# AD.net
KiCad netlist of a schematic drawn in Altium Designer
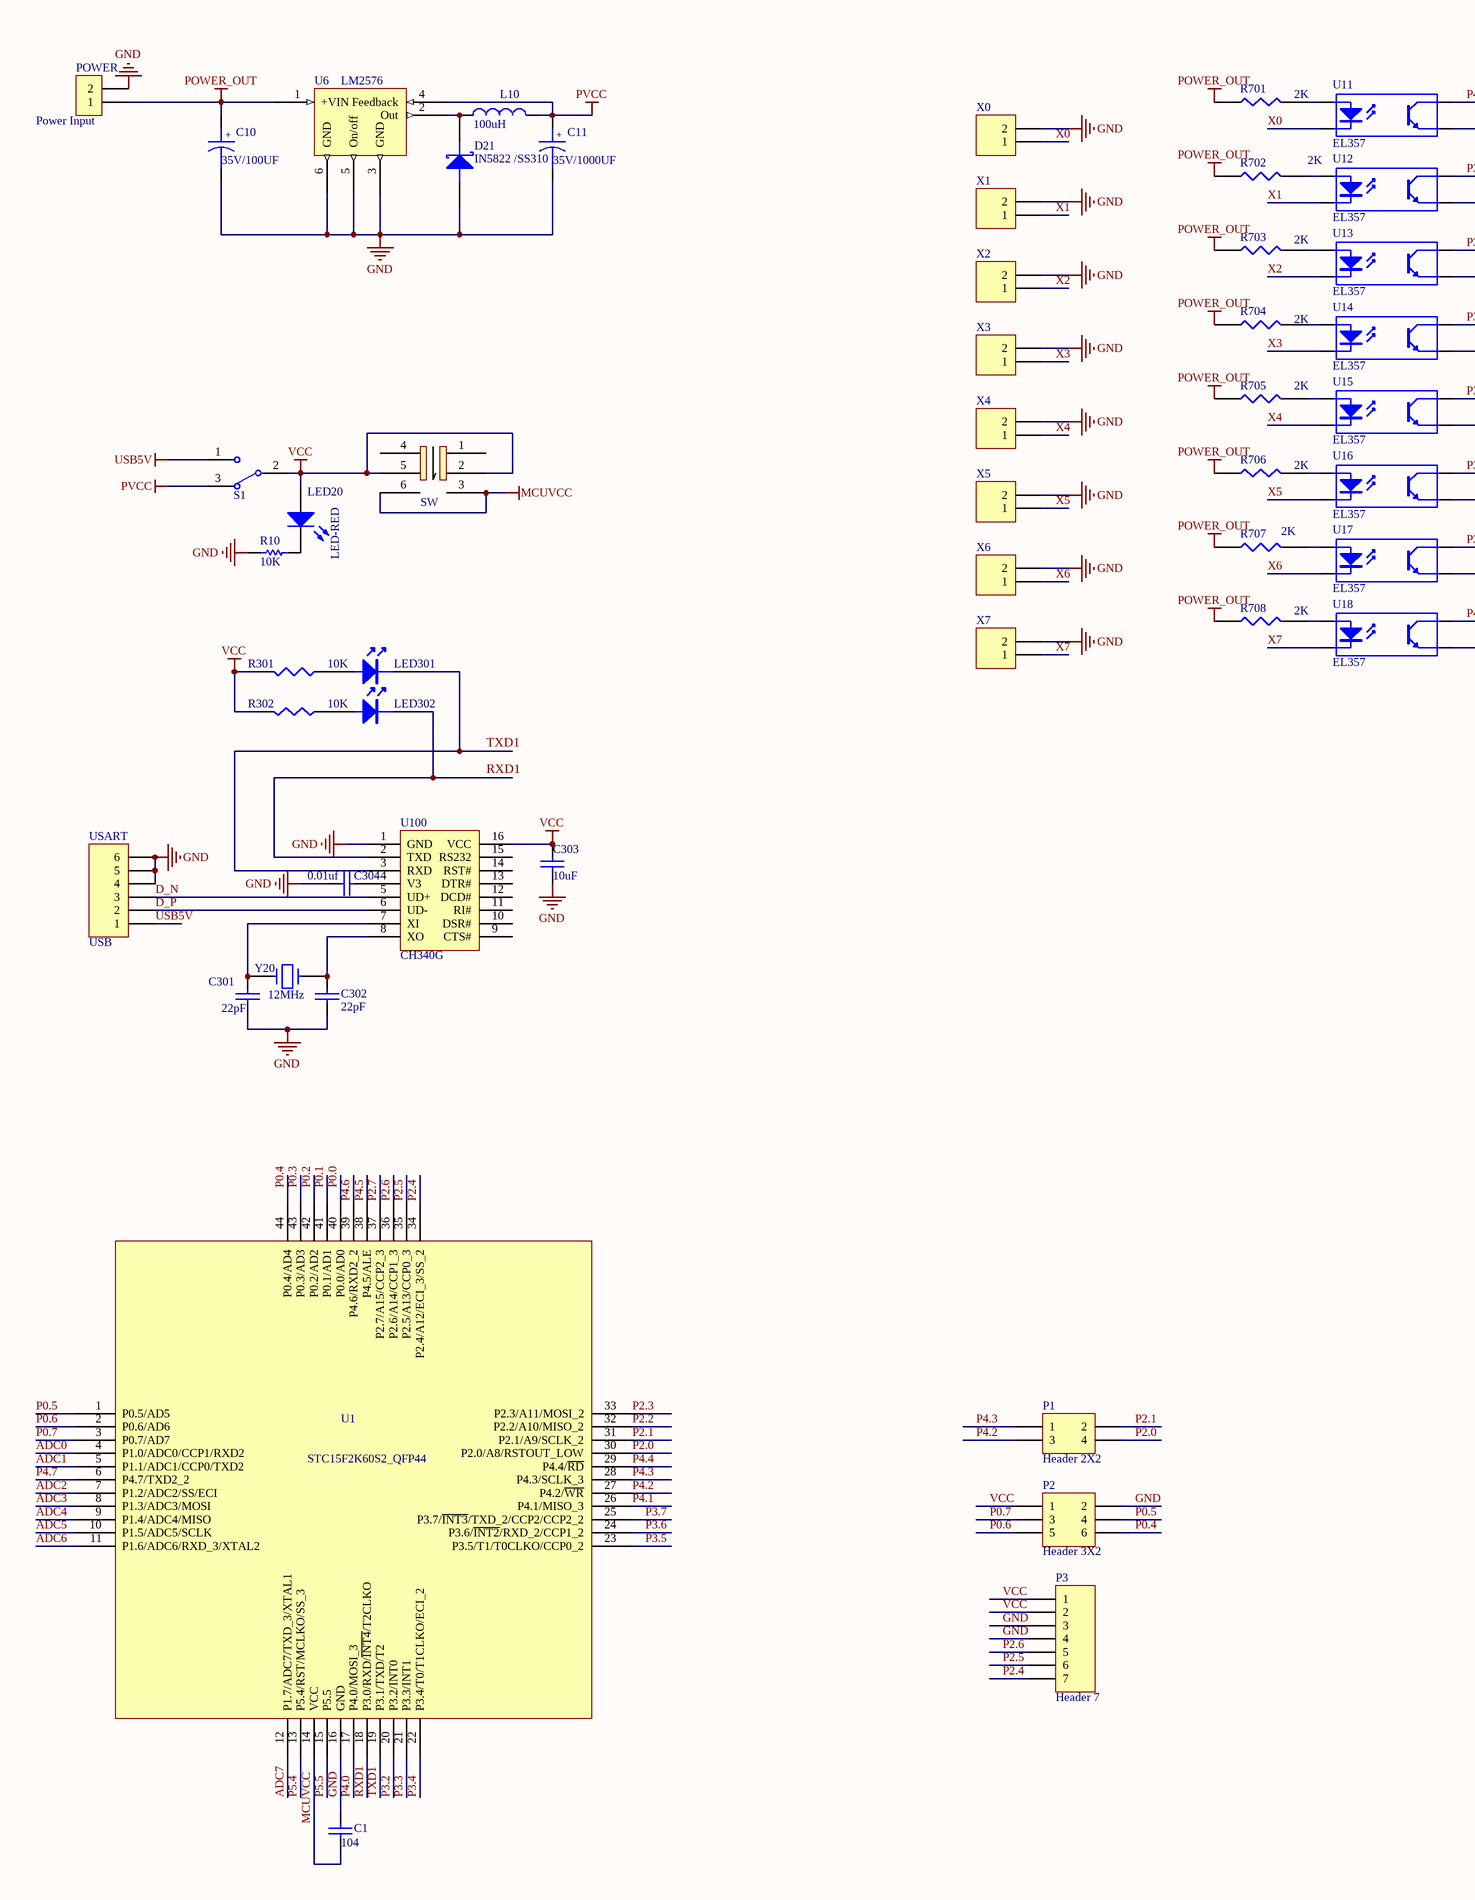
[diagram p0: AD.SchDoc, left]
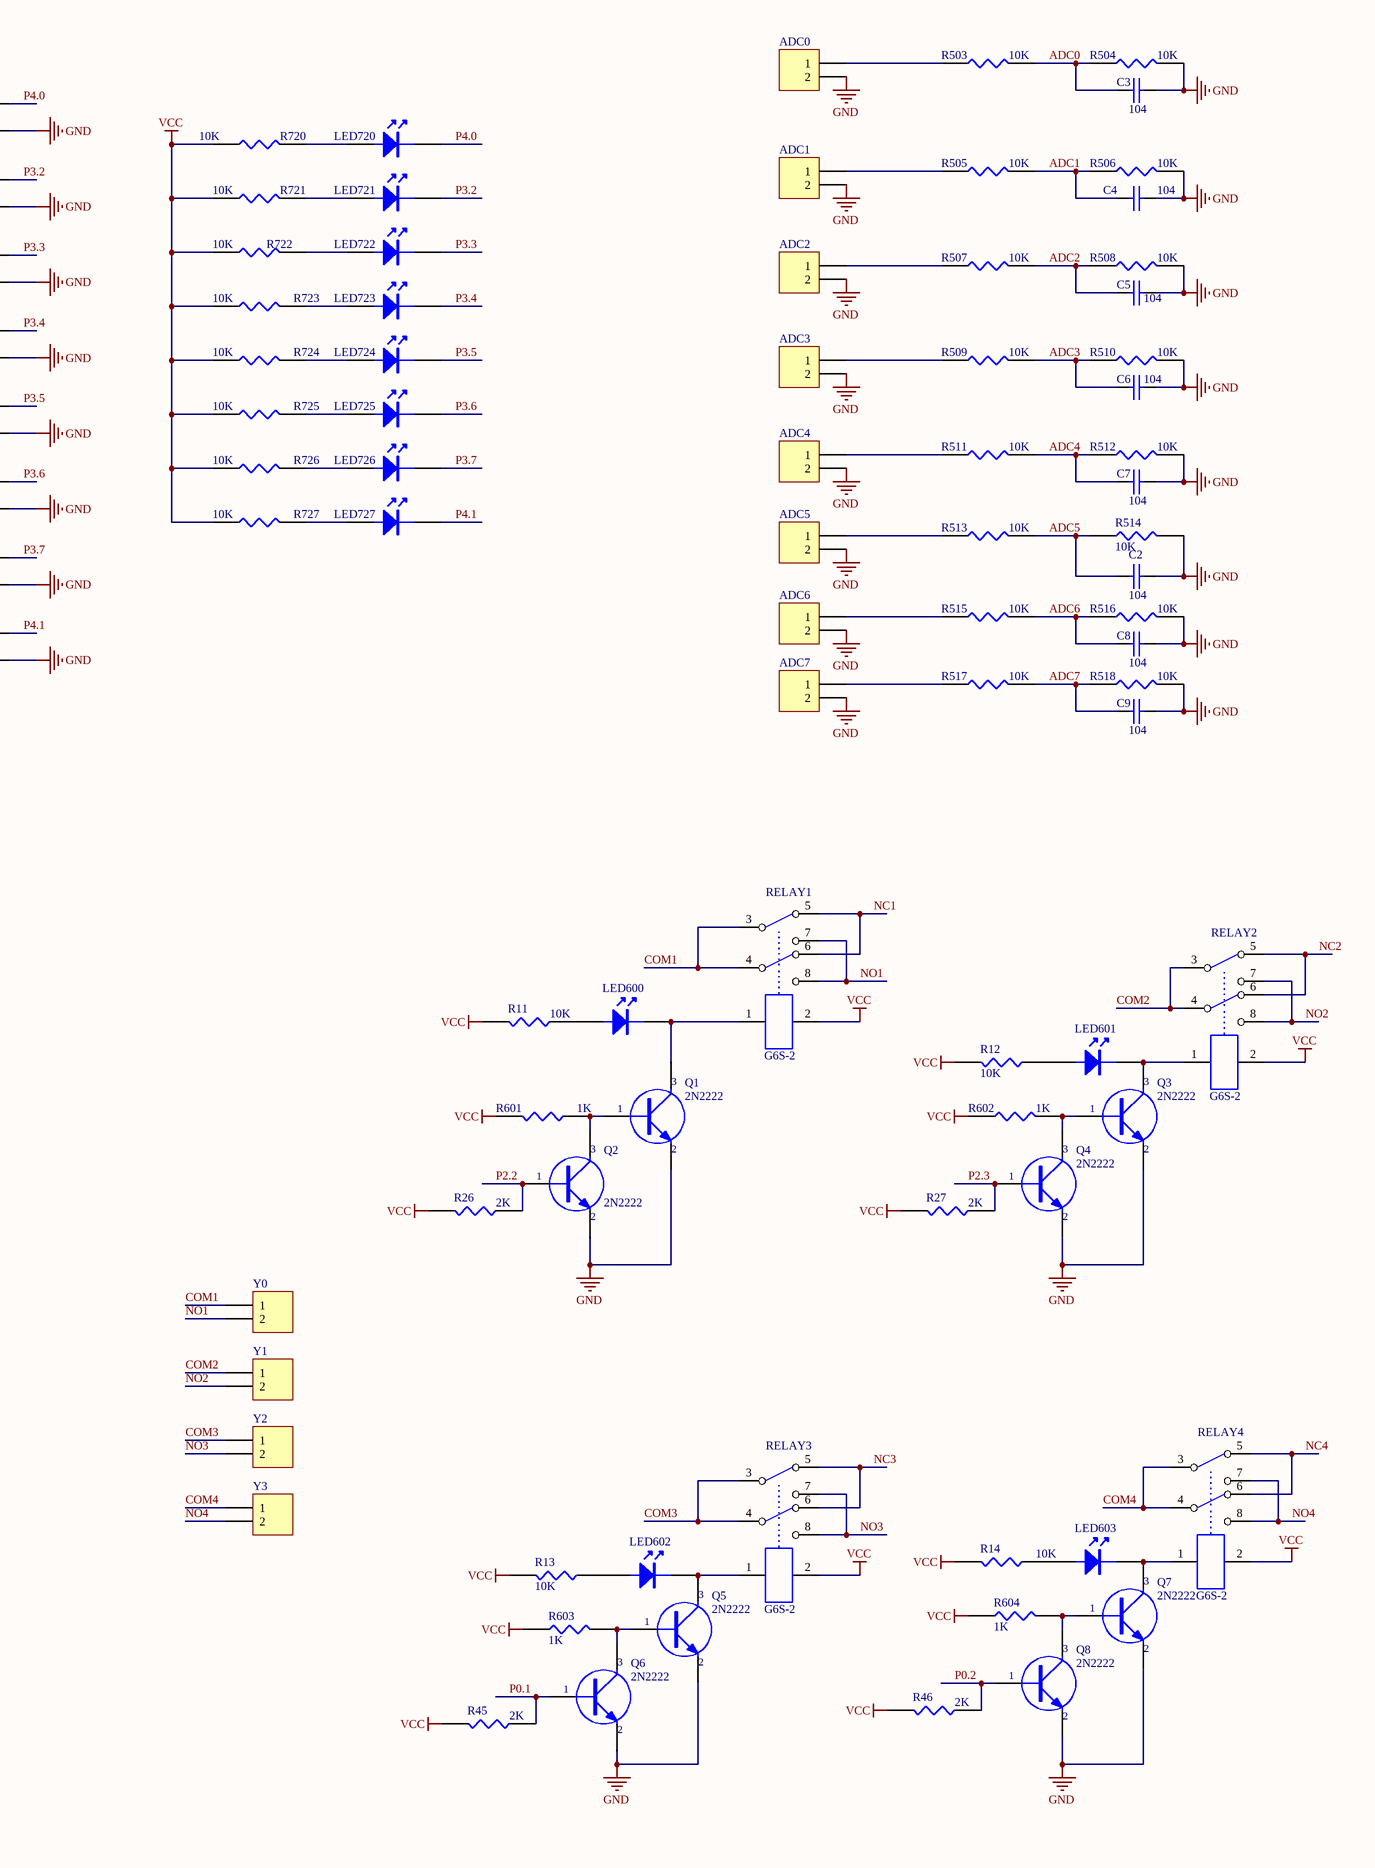
[diagram p1: AD.SchDoc, right]

(export (version "E")
  (design (tool "Eeschema 10.0.6"))
  (components
    (comp (ref "ADC0")
      (value "ADC")
      (footprint "CON2_1")
      (description "Header, 2-Pin")
      (fields (field (name "PUBLISHER") "Altium Limited"))
      (libsource (lib "") (part "Header 2_2"))
    )
    (comp (ref "ADC1")
      (value "ADC")
      (footprint "CON2_1")
      (description "Header, 2-Pin")
      (fields (field (name "PUBLISHER") "Altium Limited"))
      (libsource (lib "") (part "Header 2_2"))
    )
    (comp (ref "ADC2")
      (value "ADC")
      (footprint "CON2_1")
      (description "Header, 2-Pin")
      (fields (field (name "PUBLISHER") "Altium Limited"))
      (libsource (lib "") (part "Header 2_2"))
    )
    (comp (ref "ADC3")
      (value "ADC")
      (footprint "CON2_1")
      (description "Header, 2-Pin")
      (fields (field (name "PUBLISHER") "Altium Limited"))
      (libsource (lib "") (part "Header 2_2"))
    )
    (comp (ref "ADC4")
      (value "ADC")
      (footprint "CON2_1")
      (description "Header, 2-Pin")
      (fields (field (name "PUBLISHER") "Altium Limited"))
      (libsource (lib "") (part "Header 2_2"))
    )
    (comp (ref "ADC5")
      (value "ADC")
      (footprint "CON2_1")
      (description "Header, 2-Pin")
      (fields (field (name "PUBLISHER") "Altium Limited"))
      (libsource (lib "") (part "Header 2_2"))
    )
    (comp (ref "ADC6")
      (value "ADC")
      (footprint "CON2_1")
      (description "Header, 2-Pin")
      (fields (field (name "PUBLISHER") "Altium Limited"))
      (libsource (lib "") (part "Header 2_2"))
    )
    (comp (ref "ADC7")
      (value "ADC")
      (footprint "CON2_1")
      (description "Header, 2-Pin")
      (fields (field (name "PUBLISHER") "Altium Limited"))
      (libsource (lib "") (part "Header 2_2"))
    )
    (comp (ref "C1") (value "104") (footprint "R0805") (libsource (lib "brante_zhou") (part "CAP1")))
    (comp (ref "C2") (value "104") (footprint "R0805") (libsource (lib "brante_zhou") (part "CAP1")))
    (comp (ref "C3") (value "104") (footprint "R0805") (libsource (lib "brante_zhou") (part "CAP1")))
    (comp (ref "C4") (value "104") (footprint "R0805") (libsource (lib "brante_zhou") (part "CAP1")))
    (comp (ref "C5") (value "104") (footprint "R0805") (libsource (lib "brante_zhou") (part "CAP1")))
    (comp (ref "C6") (value "104") (footprint "R0805") (libsource (lib "brante_zhou") (part "CAP1")))
    (comp (ref "C7") (value "104") (footprint "R0805") (libsource (lib "brante_zhou") (part "CAP1")))
    (comp (ref "C8") (value "104") (footprint "R0805") (libsource (lib "brante_zhou") (part "CAP1")))
    (comp (ref "C9") (value "104") (footprint "R0805") (libsource (lib "brante_zhou") (part "CAP1")))
    (comp (ref "C10") (value "35V/100UF") (footprint "RB") (libsource (lib "My_Schlib") (part "CAP2")))
    (comp (ref "C11") (value "35V/1000UF") (footprint "L-DIP") (libsource (lib "My_Schlib") (part "CAP2")))
    (comp (ref "C301") (value "22pF") (footprint "C-0805") (libsource (lib "My_Schlib") (part "CAP1")))
    (comp (ref "C302") (value "22pF") (footprint "C-0805") (libsource (lib "My_Schlib") (part "CAP1")))
    (comp (ref "C303") (value "10uF") (footprint "R0805") (libsource (lib "My_Schlib") (part "CAP1")))
    (comp (ref "C304") (value "0.01uf") (footprint "C-0805") (libsource (lib "My_Schlib") (part "CAP1")))
    (comp (ref "D21")
      (value "IN5822 /SS310")
      (footprint "DO-214AC")
      (description "Schottky Diode")
      (libsource (lib "Miscellaneous Devices") (part "DIODE SCHOTTKY"))
    )
    (comp (ref "L10")
      (value "100uH")
      (footprint "L-DIP")
      (description "Inductor")
      (fields (field (name "PUBLISHER") "Altium Limited"))
      (libsource (lib "Miscellaneous Devices") (part "Inductor"))
    )
    (comp (ref "LED20")
      (value "LED-RED")
      (footprint "led-0805")
      (description "Typical INFRARED GaAs LED")
      (fields (field (name "PUBLISHER") "Altium Limited"))
      (libsource (lib "Miscellaneous Devices") (part "LED0"))
    )
    (comp (ref "LED301") (value "~") (footprint "LED-0805") (libsource (lib "*") (part "LED")))
    (comp (ref "LED302") (value "~") (footprint "LED-0805") (libsource (lib "*") (part "LED")))
    (comp (ref "LED600") (value "~") (footprint "LED-0805") (libsource (lib "brante_zhou") (part "LED")))
    (comp (ref "LED601") (value "~") (footprint "LED-0805") (libsource (lib "brante_zhou") (part "LED")))
    (comp (ref "LED602") (value "~") (footprint "LED-0805") (libsource (lib "brante_zhou") (part "LED")))
    (comp (ref "LED603") (value "~") (footprint "LED-0805") (libsource (lib "brante_zhou") (part "LED")))
    (comp (ref "LED720") (value "LED") (footprint "LED-0805") (libsource (lib "brante_zhou") (part "LED")))
    (comp (ref "LED721") (value "LED") (footprint "LED-0805") (libsource (lib "brante_zhou") (part "LED")))
    (comp (ref "LED722") (value "LED") (footprint "LED-0805") (libsource (lib "brante_zhou") (part "LED")))
    (comp (ref "LED723") (value "LED") (footprint "LED-0805") (libsource (lib "brante_zhou") (part "LED")))
    (comp (ref "LED724") (value "LED") (footprint "LED-0805") (libsource (lib "brante_zhou") (part "LED")))
    (comp (ref "LED725") (value "LED") (footprint "LED-0805") (libsource (lib "brante_zhou") (part "LED")))
    (comp (ref "LED726") (value "LED") (footprint "LED-0805") (libsource (lib "brante_zhou") (part "LED")))
    (comp (ref "LED727") (value "LED") (footprint "LED-0805") (libsource (lib "brante_zhou") (part "LED")))
    (comp (ref "P1")
      (value "Header 2X2")
      (footprint "HDR2X2")
      (description "Header, 2-Pin, Dual row")
      (fields (field (name "PUBLISHER") "Altium Limited"))
      (libsource (lib "Miscellaneous Connectors") (part "Header 2X2"))
    )
    (comp (ref "P2")
      (value "Header 3X2")
      (footprint "HDR2X3")
      (description "Header, 3-Pin, Dual row")
      (fields (field (name "PUBLISHER") "Altium Limited"))
      (libsource (lib "Miscellaneous Connectors") (part "Header 3X2"))
    )
    (comp (ref "P3")
      (value "Header 7")
      (footprint "HDR1X7")
      (description "Header, 7-Pin")
      (fields (field (name "PUBLISHER") "Altium Limited"))
      (libsource (lib "Miscellaneous Connectors") (part "Header 7"))
    )
    (comp (ref "POWER")
      (value "Power Input")
      (footprint "CON2_1")
      (libsource (lib "brante_zhou") (part "CON2"))
    )
    (comp (ref "Q1")
      (value "2N2222")
      (footprint "SOT23A")
      (description "NPN Transistor")
      (libsource (lib "My_Schlib") (part "NPN_S8050"))
    )
    (comp (ref "Q2")
      (value "2N2222")
      (footprint "SOT23A")
      (description "NPN Transistor")
      (libsource (lib "My_Schlib") (part "NPN_S8050"))
    )
    (comp (ref "Q3")
      (value "2N2222")
      (footprint "SOT23A")
      (description "NPN Transistor")
      (libsource (lib "My_Schlib") (part "NPN_S8050"))
    )
    (comp (ref "Q4")
      (value "2N2222")
      (footprint "SOT23A")
      (description "NPN Transistor")
      (libsource (lib "My_Schlib") (part "NPN_S8050"))
    )
    (comp (ref "Q5")
      (value "2N2222")
      (footprint "SOT23A")
      (description "NPN Transistor")
      (libsource (lib "My_Schlib") (part "NPN_S8050"))
    )
    (comp (ref "Q6")
      (value "2N2222")
      (footprint "SOT23A")
      (description "NPN Transistor")
      (libsource (lib "My_Schlib") (part "NPN_S8050"))
    )
    (comp (ref "Q7")
      (value "2N2222")
      (footprint "SOT23A")
      (description "NPN Transistor")
      (libsource (lib "My_Schlib") (part "NPN_S8050"))
    )
    (comp (ref "Q8")
      (value "2N2222")
      (footprint "SOT23A")
      (description "NPN Transistor")
      (libsource (lib "My_Schlib") (part "NPN_S8050"))
    )
    (comp (ref "R10")
      (value "10K")
      (footprint "R0805")
      (description "Semiconductor Resistor")
      (fields (field (name "PUBLISHER") "Altium Limited"))
      (libsource (lib "Miscellaneous Devices") (part "Res Semi"))
    )
    (comp (ref "R11") (value "10K") (footprint "R0805") (libsource (lib "brante_zhou") (part "RES")))
    (comp (ref "R12") (value "10K") (footprint "R0805") (libsource (lib "brante_zhou") (part "RES")))
    (comp (ref "R13") (value "10K") (footprint "R0805") (libsource (lib "brante_zhou") (part "RES")))
    (comp (ref "R14") (value "10K") (footprint "R0805") (libsource (lib "brante_zhou") (part "RES")))
    (comp (ref "R26") (value "2K") (footprint "R0805") (libsource (lib "brante_zhou") (part "RES")))
    (comp (ref "R27") (value "2K") (footprint "R0805") (libsource (lib "brante_zhou") (part "RES")))
    (comp (ref "R45") (value "2K") (footprint "R0805") (libsource (lib "brante_zhou") (part "RES")))
    (comp (ref "R46") (value "2K") (footprint "R0805") (libsource (lib "brante_zhou") (part "RES")))
    (comp (ref "R301")
      (value "10K")
      (footprint "R0805")
      (description "Resistor")
      (fields (field (name "PUBLISHER") "Altium Limited"))
      (libsource (lib "Miscellaneous Devices") (part "Res3"))
    )
    (comp (ref "R302")
      (value "10K")
      (footprint "R0805")
      (description "Resistor")
      (fields (field (name "PUBLISHER") "Altium Limited"))
      (libsource (lib "Miscellaneous Devices") (part "Res3"))
    )
    (comp (ref "R503") (value "10K") (footprint "R0805") (libsource (lib "brante_zhou") (part "RES")))
    (comp (ref "R504") (value "10K") (footprint "R0805") (libsource (lib "brante_zhou") (part "RES")))
    (comp (ref "R505") (value "10K") (footprint "R0805") (libsource (lib "brante_zhou") (part "RES")))
    (comp (ref "R506") (value "10K") (footprint "R0805") (libsource (lib "brante_zhou") (part "RES")))
    (comp (ref "R507") (value "10K") (footprint "R0805") (libsource (lib "brante_zhou") (part "RES")))
    (comp (ref "R508") (value "10K") (footprint "R0805") (libsource (lib "brante_zhou") (part "RES")))
    (comp (ref "R509") (value "10K") (footprint "R0805") (libsource (lib "brante_zhou") (part "RES")))
    (comp (ref "R510") (value "10K") (footprint "R0805") (libsource (lib "brante_zhou") (part "RES")))
    (comp (ref "R511") (value "10K") (footprint "R0805") (libsource (lib "brante_zhou") (part "RES")))
    (comp (ref "R512") (value "10K") (footprint "R0805") (libsource (lib "brante_zhou") (part "RES")))
    (comp (ref "R513") (value "10K") (footprint "R0805") (libsource (lib "brante_zhou") (part "RES")))
    (comp (ref "R514") (value "10K") (footprint "R0805") (libsource (lib "brante_zhou") (part "RES")))
    (comp (ref "R515") (value "10K") (footprint "R0805") (libsource (lib "brante_zhou") (part "RES")))
    (comp (ref "R516") (value "10K") (footprint "R0805") (libsource (lib "brante_zhou") (part "RES")))
    (comp (ref "R517") (value "10K") (footprint "R0805") (libsource (lib "brante_zhou") (part "RES")))
    (comp (ref "R518") (value "10K") (footprint "R0805") (libsource (lib "brante_zhou") (part "RES")))
    (comp (ref "R601") (value "1K") (footprint "R0805") (libsource (lib "brante_zhou") (part "RES")))
    (comp (ref "R602") (value "1K") (footprint "R0805") (libsource (lib "brante_zhou") (part "RES")))
    (comp (ref "R603") (value "1K") (footprint "R0805") (libsource (lib "brante_zhou") (part "RES")))
    (comp (ref "R604") (value "1K") (footprint "R0805") (libsource (lib "brante_zhou") (part "RES")))
    (comp (ref "R701") (value "2K") (footprint "R0805") (libsource (lib "brante_zhou") (part "RES")))
    (comp (ref "R702") (value "2K") (footprint "R0805") (libsource (lib "brante_zhou") (part "RES")))
    (comp (ref "R703") (value "2K") (footprint "R0805") (libsource (lib "brante_zhou") (part "RES")))
    (comp (ref "R704") (value "2K") (footprint "R0805") (libsource (lib "brante_zhou") (part "RES")))
    (comp (ref "R705") (value "2K") (footprint "R0805") (libsource (lib "brante_zhou") (part "RES")))
    (comp (ref "R706") (value "2K") (footprint "R0805") (libsource (lib "brante_zhou") (part "RES")))
    (comp (ref "R707") (value "2K") (footprint "R0805") (libsource (lib "brante_zhou") (part "RES")))
    (comp (ref "R708") (value "2K") (footprint "R0805") (libsource (lib "brante_zhou") (part "RES")))
    (comp (ref "R720") (value "10K") (footprint "R0805") (libsource (lib "brante_zhou") (part "RES")))
    (comp (ref "R721") (value "10K") (footprint "R0805") (libsource (lib "brante_zhou") (part "RES")))
    (comp (ref "R722") (value "10K") (footprint "R0805") (libsource (lib "brante_zhou") (part "RES")))
    (comp (ref "R723") (value "10K") (footprint "R0805") (libsource (lib "brante_zhou") (part "RES")))
    (comp (ref "R724") (value "10K") (footprint "R0805") (libsource (lib "brante_zhou") (part "RES")))
    (comp (ref "R725") (value "10K") (footprint "R0805") (libsource (lib "brante_zhou") (part "RES")))
    (comp (ref "R726") (value "10K") (footprint "R0805") (libsource (lib "brante_zhou") (part "RES")))
    (comp (ref "R727") (value "10K") (footprint "R0805") (libsource (lib "brante_zhou") (part "RES")))
    (comp (ref "RELAY1")
      (value "G6S-2")
      (footprint "G6S-2")
      (libsource (lib "My_Schlib") (part "RELAY-G6S-2"))
    )
    (comp (ref "RELAY2")
      (value "G6S-2")
      (footprint "G6S-2")
      (libsource (lib "My_Schlib") (part "RELAY-G6S-2"))
    )
    (comp (ref "RELAY3")
      (value "G6S-2")
      (footprint "G6S-2")
      (libsource (lib "My_Schlib") (part "RELAY-G6S-2"))
    )
    (comp (ref "RELAY4")
      (value "G6S-2")
      (footprint "G6S-2")
      (libsource (lib "My_Schlib") (part "RELAY-G6S-2"))
    )
    (comp (ref "S1")
      (value "SW-SPDT_2")
      (footprint "SW_1")
      (description "SPDT Subminiature Toggle Switch, Right Angle Mounting, Vertical Actuation")
      (fields (field (name "PUBLISHER") "Altium Limited"))
      (libsource (lib "My_Schlib") (part "SW-SPDT_2"))
    )
    (comp (ref "SW") (value "SW") (footprint "SW") (libsource (lib "RelayBoard") (part "SW")))
    (comp (ref "U1")
      (value "STC15F2K60S2_QFP44")
      (footprint "PQFP44")
      (libsource (lib "stcmcu_altium_lib") (part "STC15F2K60S2_QFP44"))
    )
    (comp (ref "U6") (value "LM2576") (footprint "LM2576") (libsource (lib "My_Schlib") (part "LM2576")))
    (comp (ref "U11")
      (value "EL357")
      (footprint "el357")
      (description "4-Pin Phototransistor Optocoupler")
      (fields (field (name "PUBLISHER") "Altium Limited"))
      (libsource (lib "My_Schlib") (part "Optoisolator"))
    )
    (comp (ref "U12")
      (value "EL357")
      (footprint "EL357")
      (description "4-Pin Phototransistor Optocoupler")
      (fields (field (name "PUBLISHER") "Altium Limited"))
      (libsource (lib "My_Schlib") (part "Optoisolator"))
    )
    (comp (ref "U13")
      (value "EL357")
      (footprint "EL357")
      (description "4-Pin Phototransistor Optocoupler")
      (fields (field (name "PUBLISHER") "Altium Limited"))
      (libsource (lib "My_Schlib") (part "Optoisolator"))
    )
    (comp (ref "U14")
      (value "EL357")
      (footprint "EL357")
      (description "4-Pin Phototransistor Optocoupler")
      (fields (field (name "PUBLISHER") "Altium Limited"))
      (libsource (lib "My_Schlib") (part "Optoisolator"))
    )
    (comp (ref "U15")
      (value "EL357")
      (footprint "EL357")
      (description "4-Pin Phototransistor Optocoupler")
      (fields (field (name "PUBLISHER") "Altium Limited"))
      (libsource (lib "My_Schlib") (part "Optoisolator"))
    )
    (comp (ref "U16")
      (value "EL357")
      (footprint "EL357")
      (description "4-Pin Phototransistor Optocoupler")
      (fields (field (name "PUBLISHER") "Altium Limited"))
      (libsource (lib "My_Schlib") (part "Optoisolator"))
    )
    (comp (ref "U17")
      (value "EL357")
      (footprint "EL357")
      (description "4-Pin Phototransistor Optocoupler")
      (fields (field (name "PUBLISHER") "Altium Limited"))
      (libsource (lib "My_Schlib") (part "Optoisolator"))
    )
    (comp (ref "U18")
      (value "EL357")
      (footprint "EL357")
      (description "4-Pin Phototransistor Optocoupler")
      (fields (field (name "PUBLISHER") "Altium Limited"))
      (libsource (lib "My_Schlib") (part "Optoisolator"))
    )
    (comp (ref "U100") (value "CH340G") (footprint "CH340G") (libsource (lib "My_Schlib") (part "CH340G")))
    (comp (ref "USART")
      (value "USB")
      (footprint "USB2.0_A")
      (description "Header, 6-Pin")
      (fields (field (name "PUBLISHER") "Altium Limited"))
      (libsource (lib "Miscellaneous Connectors") (part "Header 6"))
    )
    (comp (ref "X0")
      (value "XH2.54")
      (footprint "con2_1")
      (description "Header, 2-Pin")
      (fields (field (name "PUBLISHER") "Altium Limited"))
      (libsource (lib "") (part "Header 2_1"))
    )
    (comp (ref "X1")
      (value "XH2.54")
      (footprint "con2_1")
      (description "Header, 2-Pin")
      (fields (field (name "PUBLISHER") "Altium Limited"))
      (libsource (lib "") (part "Header 2_1"))
    )
    (comp (ref "X2")
      (value "XH2.54")
      (footprint "con2_1")
      (description "Header, 2-Pin")
      (fields (field (name "PUBLISHER") "Altium Limited"))
      (libsource (lib "") (part "Header 2_1"))
    )
    (comp (ref "X3")
      (value "XH2.54")
      (footprint "con2_1")
      (description "Header, 2-Pin")
      (fields (field (name "PUBLISHER") "Altium Limited"))
      (libsource (lib "") (part "Header 2_1"))
    )
    (comp (ref "X4")
      (value "XH2.54")
      (footprint "con2_1")
      (description "Header, 2-Pin")
      (fields (field (name "PUBLISHER") "Altium Limited"))
      (libsource (lib "") (part "Header 2_1"))
    )
    (comp (ref "X5")
      (value "XH2.54")
      (footprint "con2_1")
      (description "Header, 2-Pin")
      (fields (field (name "PUBLISHER") "Altium Limited"))
      (libsource (lib "") (part "Header 2_1"))
    )
    (comp (ref "X6")
      (value "XH2.54")
      (footprint "con2_1")
      (description "Header, 2-Pin")
      (fields (field (name "PUBLISHER") "Altium Limited"))
      (libsource (lib "") (part "Header 2_1"))
    )
    (comp (ref "X7")
      (value "XH2.54")
      (footprint "con2_1")
      (description "Header, 2-Pin")
      (fields (field (name "PUBLISHER") "Altium Limited"))
      (libsource (lib "") (part "Header 2_1"))
    )
    (comp (ref "Y0")
      (value "Header 2")
      (footprint "CON2_1")
      (description "Header, 2-Pin")
      (fields (field (name "PUBLISHER") "Altium Limited"))
      (libsource (lib "Miscellaneous Connectors") (part "Header 2"))
    )
    (comp (ref "Y1")
      (value "Header 2")
      (footprint "CON2_1")
      (description "Header, 2-Pin")
      (fields (field (name "PUBLISHER") "Altium Limited"))
      (libsource (lib "Miscellaneous Connectors") (part "Header 2"))
    )
    (comp (ref "Y2")
      (value "Header 2")
      (footprint "CON2_1")
      (description "Header, 2-Pin")
      (fields (field (name "PUBLISHER") "Altium Limited"))
      (libsource (lib "Miscellaneous Connectors") (part "Header 2"))
    )
    (comp (ref "Y3")
      (value "Header 2")
      (footprint "CON2_1")
      (description "Header, 2-Pin")
      (fields (field (name "PUBLISHER") "Altium Limited"))
      (libsource (lib "Miscellaneous Connectors") (part "Header 2"))
    )
    (comp (ref "Y20")
      (value "12MHz")
      (footprint "XTAL1")
      (description "Crystal")
      (libsource (lib "My_Schlib") (part "CRYSTAL"))
    )
  )
  (nets
    (net (code "1") (name "/ADC0") (class "Default")
      (node (ref "C3") (pin "2") (pinfunction "2_2") (pintype "passive"))
      (node (ref "R503") (pin "2") (pinfunction "2_2") (pintype "passive"))
      (node (ref "R504") (pin "1") (pinfunction "1_1") (pintype "passive"))
      (node (ref "U1") (pin "4") (pinfunction "P1.0/ADC0/CCP1/RXD2_4") (pintype "passive"))
    )
    (net (code "2") (name "/ADC1") (class "Default")
      (node (ref "C4") (pin "2") (pinfunction "2_2") (pintype "passive"))
      (node (ref "R505") (pin "2") (pinfunction "2_2") (pintype "passive"))
      (node (ref "R506") (pin "1") (pinfunction "1_1") (pintype "passive"))
      (node (ref "U1") (pin "5") (pinfunction "P1.1/ADC1/CCP0/TXD2_5") (pintype "passive"))
    )
    (net (code "3") (name "/ADC2") (class "Default")
      (node (ref "C5") (pin "2") (pinfunction "2_2") (pintype "passive"))
      (node (ref "R507") (pin "2") (pinfunction "2_2") (pintype "passive"))
      (node (ref "R508") (pin "1") (pinfunction "1_1") (pintype "passive"))
      (node (ref "U1") (pin "7") (pinfunction "P1.2/ADC2/SS/ECI_7") (pintype "passive"))
    )
    (net (code "4") (name "/ADC3") (class "Default")
      (node (ref "C6") (pin "2") (pinfunction "2_2") (pintype "passive"))
      (node (ref "R509") (pin "2") (pinfunction "2_2") (pintype "passive"))
      (node (ref "R510") (pin "1") (pinfunction "1_1") (pintype "passive"))
      (node (ref "U1") (pin "8") (pinfunction "P1.3/ADC3/MOSI_8") (pintype "passive"))
    )
    (net (code "5") (name "/ADC4") (class "Default")
      (node (ref "C7") (pin "2") (pinfunction "2_2") (pintype "passive"))
      (node (ref "R511") (pin "2") (pinfunction "2_2") (pintype "passive"))
      (node (ref "R512") (pin "1") (pinfunction "1_1") (pintype "passive"))
      (node (ref "U1") (pin "9") (pinfunction "P1.4/ADC4/MISO_9") (pintype "passive"))
    )
    (net (code "6") (name "/ADC5") (class "Default")
      (node (ref "C2") (pin "1") (pinfunction "1_1") (pintype "passive"))
      (node (ref "R513") (pin "2") (pinfunction "2_2") (pintype "passive"))
      (node (ref "R514") (pin "1") (pinfunction "1_1") (pintype "passive"))
      (node (ref "U1") (pin "10") (pinfunction "P1.5/ADC5/SCLK_10") (pintype "passive"))
    )
    (net (code "7") (name "/ADC6") (class "Default")
      (node (ref "C8") (pin "2") (pinfunction "2_2") (pintype "passive"))
      (node (ref "R515") (pin "2") (pinfunction "2_2") (pintype "passive"))
      (node (ref "R516") (pin "1") (pinfunction "1_1") (pintype "passive"))
      (node (ref "U1") (pin "11") (pinfunction "P1.6/ADC6/RXD_3/XTAL2_11") (pintype "passive"))
    )
    (net (code "8") (name "/ADC7") (class "Default")
      (node (ref "C9") (pin "2") (pinfunction "2_2") (pintype "passive"))
      (node (ref "R517") (pin "2") (pinfunction "2_2") (pintype "passive"))
      (node (ref "R518") (pin "1") (pinfunction "1_1") (pintype "passive"))
      (node (ref "U1") (pin "12") (pinfunction "P1.7/ADC7/TXD_3/XTAL1_12") (pintype "passive"))
    )
    (net (code "9") (name "/COM1") (class "Default")
      (node (ref "RELAY1") (pin "3") (pinfunction "3_3") (pintype "passive"))
      (node (ref "RELAY1") (pin "4") (pinfunction "4_4") (pintype "passive"))
      (node (ref "Y0") (pin "1") (pinfunction "1_1") (pintype "passive"))
    )
    (net (code "10") (name "/COM2") (class "Default")
      (node (ref "RELAY2") (pin "3") (pinfunction "3_3") (pintype "passive"))
      (node (ref "RELAY2") (pin "4") (pinfunction "4_4") (pintype "passive"))
      (node (ref "Y1") (pin "1") (pinfunction "1_1") (pintype "passive"))
    )
    (net (code "11") (name "/COM3") (class "Default")
      (node (ref "RELAY3") (pin "3") (pinfunction "3_3") (pintype "passive"))
      (node (ref "RELAY3") (pin "4") (pinfunction "4_4") (pintype "passive"))
      (node (ref "Y2") (pin "1") (pinfunction "1_1") (pintype "passive"))
    )
    (net (code "12") (name "/COM4") (class "Default")
      (node (ref "RELAY4") (pin "3") (pinfunction "3_3") (pintype "passive"))
      (node (ref "RELAY4") (pin "4") (pinfunction "4_4") (pintype "passive"))
      (node (ref "Y3") (pin "1") (pinfunction "1_1") (pintype "passive"))
    )
    (net (code "13") (name "/D_N") (class "Default")
      (node (ref "U100") (pin "5") (pinfunction "UD+_5") (pintype "passive"))
      (node (ref "USART") (pin "3") (pinfunction "3_3") (pintype "passive"))
    )
    (net (code "14") (name "/D_P") (class "Default")
      (node (ref "U100") (pin "6") (pinfunction "UD-_6") (pintype "passive"))
      (node (ref "USART") (pin "2") (pinfunction "2_2") (pintype "passive"))
    )
    (net (code "15") (name "/NC1") (class "Default")
      (node (ref "RELAY1") (pin "5") (pinfunction "5_5") (pintype "passive"))
      (node (ref "RELAY1") (pin "6") (pinfunction "6_6") (pintype "passive"))
    )
    (net (code "16") (name "/NC2") (class "Default")
      (node (ref "RELAY2") (pin "5") (pinfunction "5_5") (pintype "passive"))
      (node (ref "RELAY2") (pin "6") (pinfunction "6_6") (pintype "passive"))
    )
    (net (code "17") (name "/NC3") (class "Default")
      (node (ref "RELAY3") (pin "5") (pinfunction "5_5") (pintype "passive"))
      (node (ref "RELAY3") (pin "6") (pinfunction "6_6") (pintype "passive"))
    )
    (net (code "18") (name "/NC4") (class "Default")
      (node (ref "RELAY4") (pin "5") (pinfunction "5_5") (pintype "passive"))
      (node (ref "RELAY4") (pin "6") (pinfunction "6_6") (pintype "passive"))
    )
    (net (code "19") (name "/NO1") (class "Default")
      (node (ref "RELAY1") (pin "7") (pinfunction "7_7") (pintype "passive"))
      (node (ref "RELAY1") (pin "8") (pinfunction "8_8") (pintype "passive"))
      (node (ref "Y0") (pin "2") (pinfunction "2_2") (pintype "passive"))
    )
    (net (code "20") (name "/NO2") (class "Default")
      (node (ref "RELAY2") (pin "7") (pinfunction "7_7") (pintype "passive"))
      (node (ref "RELAY2") (pin "8") (pinfunction "8_8") (pintype "passive"))
      (node (ref "Y1") (pin "2") (pinfunction "2_2") (pintype "passive"))
    )
    (net (code "21") (name "/NO3") (class "Default")
      (node (ref "RELAY3") (pin "7") (pinfunction "7_7") (pintype "passive"))
      (node (ref "RELAY3") (pin "8") (pinfunction "8_8") (pintype "passive"))
      (node (ref "Y2") (pin "2") (pinfunction "2_2") (pintype "passive"))
    )
    (net (code "22") (name "/NO4") (class "Default")
      (node (ref "RELAY4") (pin "7") (pinfunction "7_7") (pintype "passive"))
      (node (ref "RELAY4") (pin "8") (pinfunction "8_8") (pintype "passive"))
      (node (ref "Y3") (pin "2") (pinfunction "2_2") (pintype "passive"))
    )
    (net (code "23") (name "/P0.0") (class "Default")
      (node (ref "U1") (pin "40") (pinfunction "P0.0/AD0_40") (pintype "passive"))
    )
    (net (code "24") (name "/P0.1") (class "Default")
      (node (ref "Q6") (pin "1") (pinfunction "B_1") (pintype "passive"))
      (node (ref "R45") (pin "1") (pinfunction "1_1") (pintype "passive"))
      (node (ref "U1") (pin "41") (pinfunction "P0.1/AD1_41") (pintype "passive"))
    )
    (net (code "25") (name "/P0.2") (class "Default")
      (node (ref "Q8") (pin "1") (pinfunction "B_1") (pintype "passive"))
      (node (ref "R46") (pin "1") (pinfunction "1_1") (pintype "passive"))
      (node (ref "U1") (pin "42") (pinfunction "P0.2/AD2_42") (pintype "passive"))
    )
    (net (code "26") (name "/P0.3") (class "Default")
      (node (ref "U1") (pin "43") (pinfunction "P0.3/AD3_43") (pintype "passive"))
    )
    (net (code "27") (name "/P0.4") (class "Default")
      (node (ref "P2") (pin "6") (pinfunction "6_6") (pintype "passive"))
      (node (ref "U1") (pin "44") (pinfunction "P0.4/AD4_44") (pintype "passive"))
    )
    (net (code "28") (name "/P0.5") (class "Default")
      (node (ref "P2") (pin "4") (pinfunction "4_4") (pintype "passive"))
      (node (ref "U1") (pin "1") (pinfunction "P0.5/AD5_1") (pintype "passive"))
    )
    (net (code "29") (name "/P0.6") (class "Default")
      (node (ref "P2") (pin "5") (pinfunction "5_5") (pintype "passive"))
      (node (ref "U1") (pin "2") (pinfunction "P0.6/AD6_2") (pintype "passive"))
    )
    (net (code "30") (name "/P0.7") (class "Default")
      (node (ref "P2") (pin "3") (pinfunction "3_3") (pintype "passive"))
      (node (ref "U1") (pin "3") (pinfunction "P0.7/AD7_3") (pintype "passive"))
    )
    (net (code "31") (name "/P2.0") (class "Default")
      (node (ref "P1") (pin "4") (pinfunction "4_4") (pintype "passive"))
      (node (ref "U1") (pin "30") (pinfunction "P2.0/A8/RSTOUT_LOW_30") (pintype "passive"))
    )
    (net (code "32") (name "/P2.1") (class "Default")
      (node (ref "P1") (pin "2") (pinfunction "2_2") (pintype "passive"))
      (node (ref "U1") (pin "31") (pinfunction "P2.1/A9/SCLK_2_31") (pintype "passive"))
    )
    (net (code "33") (name "/P2.2") (class "Default")
      (node (ref "Q2") (pin "1") (pinfunction "B_1") (pintype "passive"))
      (node (ref "R26") (pin "1") (pinfunction "1_1") (pintype "passive"))
      (node (ref "U1") (pin "32") (pinfunction "P2.2/A10/MISO_2_32") (pintype "passive"))
    )
    (net (code "34") (name "/P2.3") (class "Default")
      (node (ref "Q4") (pin "1") (pinfunction "B_1") (pintype "passive"))
      (node (ref "R27") (pin "1") (pinfunction "1_1") (pintype "passive"))
      (node (ref "U1") (pin "33") (pinfunction "P2.3/A11/MOSI_2_33") (pintype "passive"))
    )
    (net (code "35") (name "/P2.4") (class "Default")
      (node (ref "P3") (pin "7") (pinfunction "7_7") (pintype "passive"))
      (node (ref "U1") (pin "34") (pinfunction "P2.4/A12/ECI_3/SS_2_34") (pintype "passive"))
    )
    (net (code "36") (name "/P2.5") (class "Default")
      (node (ref "P3") (pin "6") (pinfunction "6_6") (pintype "passive"))
      (node (ref "U1") (pin "35") (pinfunction "P2.5/A13/CCP0_3_35") (pintype "passive"))
    )
    (net (code "37") (name "/P2.6") (class "Default")
      (node (ref "P3") (pin "5") (pinfunction "5_5") (pintype "passive"))
      (node (ref "U1") (pin "36") (pinfunction "P2.6/A14/CCP1_3_36") (pintype "passive"))
    )
    (net (code "38") (name "/P2.7") (class "Default")
      (node (ref "U1") (pin "37") (pinfunction "P2.7/A15/CCP2_3_37") (pintype "passive"))
    )
    (net (code "39") (name "/P3.2") (class "Default")
      (node (ref "LED721") (pin "2") (pinfunction "2_2") (pintype "passive"))
      (node (ref "U1") (pin "20") (pinfunction "P3.2/INT0_20") (pintype "passive"))
      (node (ref "U12") (pin "4") (pinfunction "C_4") (pintype "passive"))
    )
    (net (code "40") (name "/P3.3") (class "Default")
      (node (ref "LED722") (pin "2") (pinfunction "2_2") (pintype "passive"))
      (node (ref "U1") (pin "21") (pinfunction "P3.3/INT1_21") (pintype "passive"))
      (node (ref "U13") (pin "4") (pinfunction "C_4") (pintype "passive"))
    )
    (net (code "41") (name "/P3.4") (class "Default")
      (node (ref "LED723") (pin "2") (pinfunction "2_2") (pintype "passive"))
      (node (ref "U1") (pin "22") (pinfunction "P3.4/T0/T1CLKO/ECI_2_22") (pintype "passive"))
      (node (ref "U14") (pin "4") (pinfunction "C_4") (pintype "passive"))
    )
    (net (code "42") (name "/P3.5") (class "Default")
      (node (ref "LED724") (pin "2") (pinfunction "2_2") (pintype "passive"))
      (node (ref "U1") (pin "23") (pinfunction "P3.5/T1/T0CLKO/CCP0_2_23") (pintype "passive"))
      (node (ref "U15") (pin "4") (pinfunction "C_4") (pintype "passive"))
    )
    (net (code "43") (name "/P3.6") (class "Default")
      (node (ref "LED725") (pin "2") (pinfunction "2_2") (pintype "passive"))
      (node (ref "U1") (pin "24") (pinfunction "P3.6/~{INT2}/RXD_2/CCP1_2_24") (pintype "passive"))
      (node (ref "U16") (pin "4") (pinfunction "C_4") (pintype "passive"))
    )
    (net (code "44") (name "/P3.7") (class "Default")
      (node (ref "LED726") (pin "2") (pinfunction "2_2") (pintype "passive"))
      (node (ref "U1") (pin "25") (pinfunction "P3.7/~{INT3}/TXD_2/CCP2/CCP2_2_25") (pintype "passive"))
      (node (ref "U17") (pin "4") (pinfunction "C_4") (pintype "passive"))
    )
    (net (code "45") (name "/P4.0") (class "Default")
      (node (ref "LED720") (pin "2") (pinfunction "2_2") (pintype "passive"))
      (node (ref "U1") (pin "17") (pinfunction "P4.0/MOSI_3_17") (pintype "passive"))
      (node (ref "U11") (pin "4") (pinfunction "C_4") (pintype "passive"))
    )
    (net (code "46") (name "/P4.1") (class "Default")
      (node (ref "LED727") (pin "2") (pinfunction "2_2") (pintype "passive"))
      (node (ref "U1") (pin "26") (pinfunction "P4.1/MISO_3_26") (pintype "passive"))
      (node (ref "U18") (pin "4") (pinfunction "C_4") (pintype "passive"))
    )
    (net (code "47") (name "/P4.2") (class "Default")
      (node (ref "P1") (pin "3") (pinfunction "3_3") (pintype "passive"))
      (node (ref "U1") (pin "27") (pinfunction "P4.2/~{WR}_27") (pintype "passive"))
    )
    (net (code "48") (name "/P4.3") (class "Default")
      (node (ref "P1") (pin "1") (pinfunction "1_1") (pintype "passive"))
      (node (ref "U1") (pin "28") (pinfunction "P4.3/SCLK_3_28") (pintype "passive"))
    )
    (net (code "49") (name "/P4.4") (class "Default")
      (node (ref "U1") (pin "29") (pinfunction "P4.4/~{RD}_29") (pintype "passive"))
    )
    (net (code "50") (name "/P4.5") (class "Default")
      (node (ref "U1") (pin "38") (pinfunction "P4.5/ALE_38") (pintype "passive"))
    )
    (net (code "51") (name "/P4.6") (class "Default")
      (node (ref "U1") (pin "39") (pinfunction "P4.6/RXD2_2_39") (pintype "passive"))
    )
    (net (code "52") (name "/P4.7") (class "Default")
      (node (ref "U1") (pin "6") (pinfunction "P4.7/TXD2_2_6") (pintype "passive"))
    )
    (net (code "53") (name "/P5.4") (class "Default")
      (node (ref "U1") (pin "13") (pinfunction "P5.4/RST/MCLKO/SS_3_13") (pintype "passive"))
    )
    (net (code "54") (name "/P5.5") (class "Default")
      (node (ref "U1") (pin "15") (pinfunction "P5.5_15") (pintype "passive"))
    )
    (net (code "55") (name "/RXD1") (class "Default")
      (node (ref "LED302") (pin "2") (pinfunction "2_2") (pintype "passive"))
      (node (ref "U1") (pin "18") (pinfunction "P3.0/RXD/~{INT4}/T2CLKO_18") (pintype "passive"))
      (node (ref "U100") (pin "2") (pinfunction "TXD_2") (pintype "passive"))
    )
    (net (code "56") (name "/TXD1") (class "Default")
      (node (ref "LED301") (pin "2") (pinfunction "2_2") (pintype "passive"))
      (node (ref "U1") (pin "19") (pinfunction "P3.1/TXD/T2_19") (pintype "passive"))
      (node (ref "U100") (pin "3") (pinfunction "RXD_3") (pintype "passive"))
    )
    (net (code "57") (name "/X0") (class "Default")
      (node (ref "U11") (pin "2") (pinfunction "K_2") (pintype "passive"))
      (node (ref "X0") (pin "1") (pinfunction "1_1") (pintype "passive"))
    )
    (net (code "58") (name "/X1") (class "Default")
      (node (ref "U12") (pin "2") (pinfunction "K_2") (pintype "passive"))
      (node (ref "X1") (pin "1") (pinfunction "1_1") (pintype "passive"))
    )
    (net (code "59") (name "/X2") (class "Default")
      (node (ref "U13") (pin "2") (pinfunction "K_2") (pintype "passive"))
      (node (ref "X2") (pin "1") (pinfunction "1_1") (pintype "passive"))
    )
    (net (code "60") (name "/X3") (class "Default")
      (node (ref "U14") (pin "2") (pinfunction "K_2") (pintype "passive"))
      (node (ref "X3") (pin "1") (pinfunction "1_1") (pintype "passive"))
    )
    (net (code "61") (name "/X4") (class "Default")
      (node (ref "U15") (pin "2") (pinfunction "K_2") (pintype "passive"))
      (node (ref "X4") (pin "1") (pinfunction "1_1") (pintype "passive"))
    )
    (net (code "62") (name "/X5") (class "Default")
      (node (ref "U16") (pin "2") (pinfunction "K_2") (pintype "passive"))
      (node (ref "X5") (pin "1") (pinfunction "1_1") (pintype "passive"))
    )
    (net (code "63") (name "/X6") (class "Default")
      (node (ref "U17") (pin "2") (pinfunction "K_2") (pintype "passive"))
      (node (ref "X6") (pin "1") (pinfunction "1_1") (pintype "passive"))
    )
    (net (code "64") (name "/X7") (class "Default")
      (node (ref "U18") (pin "2") (pinfunction "K_2") (pintype "passive"))
      (node (ref "X7") (pin "1") (pinfunction "1_1") (pintype "passive"))
    )
    (net (code "65") (name "GND") (class "Default")
      (node (ref "ADC0") (pin "2") (pinfunction "2_2") (pintype "passive"))
      (node (ref "ADC1") (pin "2") (pinfunction "2_2") (pintype "passive"))
      (node (ref "ADC2") (pin "2") (pinfunction "2_2") (pintype "passive"))
      (node (ref "ADC3") (pin "2") (pinfunction "2_2") (pintype "passive"))
      (node (ref "ADC4") (pin "2") (pinfunction "2_2") (pintype "passive"))
      (node (ref "ADC5") (pin "2") (pinfunction "2_2") (pintype "passive"))
      (node (ref "ADC6") (pin "2") (pinfunction "2_2") (pintype "passive"))
      (node (ref "ADC7") (pin "2") (pinfunction "2_2") (pintype "passive"))
      (node (ref "C1") (pin "2") (pinfunction "2_2") (pintype "passive"))
      (node (ref "C10") (pin "2") (pinfunction "2_2") (pintype "passive"))
      (node (ref "C11") (pin "2") (pinfunction "2_2") (pintype "passive"))
      (node (ref "C2") (pin "2") (pinfunction "2_2") (pintype "passive"))
      (node (ref "C3") (pin "1") (pinfunction "1_1") (pintype "passive"))
      (node (ref "C301") (pin "2") (pinfunction "2_2") (pintype "passive"))
      (node (ref "C302") (pin "2") (pinfunction "2_2") (pintype "passive"))
      (node (ref "C303") (pin "2") (pinfunction "2_2") (pintype "passive"))
      (node (ref "C304") (pin "1") (pinfunction "1_1") (pintype "passive"))
      (node (ref "C4") (pin "1") (pinfunction "1_1") (pintype "passive"))
      (node (ref "C5") (pin "1") (pinfunction "1_1") (pintype "passive"))
      (node (ref "C6") (pin "1") (pinfunction "1_1") (pintype "passive"))
      (node (ref "C7") (pin "1") (pinfunction "1_1") (pintype "passive"))
      (node (ref "C8") (pin "1") (pinfunction "1_1") (pintype "passive"))
      (node (ref "C9") (pin "1") (pinfunction "1_1") (pintype "passive"))
      (node (ref "D21") (pin "1") (pinfunction "A_1") (pintype "passive"))
      (node (ref "P2") (pin "2") (pinfunction "2_2") (pintype "passive"))
      (node (ref "P3") (pin "3") (pinfunction "3_3") (pintype "passive"))
      (node (ref "P3") (pin "4") (pinfunction "4_4") (pintype "passive"))
      (node (ref "POWER") (pin "2") (pinfunction "2_2") (pintype "passive"))
      (node (ref "Q1") (pin "2") (pinfunction "E_2") (pintype "passive"))
      (node (ref "Q2") (pin "2") (pinfunction "E_2") (pintype "passive"))
      (node (ref "Q3") (pin "2") (pinfunction "E_2") (pintype "passive"))
      (node (ref "Q4") (pin "2") (pinfunction "E_2") (pintype "passive"))
      (node (ref "Q5") (pin "2") (pinfunction "E_2") (pintype "passive"))
      (node (ref "Q6") (pin "2") (pinfunction "E_2") (pintype "passive"))
      (node (ref "Q7") (pin "2") (pinfunction "E_2") (pintype "passive"))
      (node (ref "Q8") (pin "2") (pinfunction "E_2") (pintype "passive"))
      (node (ref "R10") (pin "1") (pinfunction "1_1") (pintype "passive"))
      (node (ref "R504") (pin "2") (pinfunction "2_2") (pintype "passive"))
      (node (ref "R506") (pin "2") (pinfunction "2_2") (pintype "passive"))
      (node (ref "R508") (pin "2") (pinfunction "2_2") (pintype "passive"))
      (node (ref "R510") (pin "2") (pinfunction "2_2") (pintype "passive"))
      (node (ref "R512") (pin "2") (pinfunction "2_2") (pintype "passive"))
      (node (ref "R514") (pin "2") (pinfunction "2_2") (pintype "passive"))
      (node (ref "R516") (pin "2") (pinfunction "2_2") (pintype "passive"))
      (node (ref "R518") (pin "2") (pinfunction "2_2") (pintype "passive"))
      (node (ref "U1") (pin "16") (pinfunction "GND_16") (pintype "passive"))
      (node (ref "U100") (pin "1") (pinfunction "GND_1") (pintype "power_in"))
      (node (ref "U11") (pin "3") (pinfunction "E_3") (pintype "passive"))
      (node (ref "U12") (pin "3") (pinfunction "E_3") (pintype "passive"))
      (node (ref "U13") (pin "3") (pinfunction "E_3") (pintype "passive"))
      (node (ref "U14") (pin "3") (pinfunction "E_3") (pintype "passive"))
      (node (ref "U15") (pin "3") (pinfunction "E_3") (pintype "passive"))
      (node (ref "U16") (pin "3") (pinfunction "E_3") (pintype "passive"))
      (node (ref "U17") (pin "3") (pinfunction "E_3") (pintype "passive"))
      (node (ref "U18") (pin "3") (pinfunction "E_3") (pintype "passive"))
      (node (ref "U6") (pin "3") (pinfunction "GND_3") (pintype "output"))
      (node (ref "U6") (pin "5") (pinfunction "On/off_5") (pintype "output"))
      (node (ref "U6") (pin "6") (pinfunction "GND_6") (pintype "output"))
      (node (ref "USART") (pin "4") (pinfunction "4_4") (pintype "passive"))
      (node (ref "USART") (pin "5") (pinfunction "5_5") (pintype "passive"))
      (node (ref "USART") (pin "6") (pinfunction "6_6") (pintype "passive"))
      (node (ref "X0") (pin "2") (pinfunction "2_2") (pintype "passive"))
      (node (ref "X1") (pin "2") (pinfunction "2_2") (pintype "passive"))
      (node (ref "X2") (pin "2") (pinfunction "2_2") (pintype "passive"))
      (node (ref "X3") (pin "2") (pinfunction "2_2") (pintype "passive"))
      (node (ref "X4") (pin "2") (pinfunction "2_2") (pintype "passive"))
      (node (ref "X5") (pin "2") (pinfunction "2_2") (pintype "passive"))
      (node (ref "X6") (pin "2") (pinfunction "2_2") (pintype "passive"))
      (node (ref "X7") (pin "2") (pinfunction "2_2") (pintype "passive"))
    )
    (net (code "66") (name "MCUVCC") (class "Default")
      (node (ref "C1") (pin "1") (pinfunction "1_1") (pintype "passive"))
      (node (ref "SW") (pin "3") (pinfunction "3_3") (pintype "passive"))
      (node (ref "SW") (pin "6") (pinfunction "6_6") (pintype "passive"))
      (node (ref "U1") (pin "14") (pinfunction "VCC_14") (pintype "passive"))
    )
    (net (code "67") (name "Net-(ADC0-Pad1)") (class "Default")
      (node (ref "ADC0") (pin "1") (pinfunction "1_1") (pintype "passive"))
      (node (ref "R503") (pin "1") (pinfunction "1_1") (pintype "passive"))
    )
    (net (code "68") (name "Net-(ADC1-Pad1)") (class "Default")
      (node (ref "ADC1") (pin "1") (pinfunction "1_1") (pintype "passive"))
      (node (ref "R505") (pin "1") (pinfunction "1_1") (pintype "passive"))
    )
    (net (code "69") (name "Net-(ADC2-Pad1)") (class "Default")
      (node (ref "ADC2") (pin "1") (pinfunction "1_1") (pintype "passive"))
      (node (ref "R507") (pin "1") (pinfunction "1_1") (pintype "passive"))
    )
    (net (code "70") (name "Net-(ADC3-Pad1)") (class "Default")
      (node (ref "ADC3") (pin "1") (pinfunction "1_1") (pintype "passive"))
      (node (ref "R509") (pin "1") (pinfunction "1_1") (pintype "passive"))
    )
    (net (code "71") (name "Net-(ADC4-Pad1)") (class "Default")
      (node (ref "ADC4") (pin "1") (pinfunction "1_1") (pintype "passive"))
      (node (ref "R511") (pin "1") (pinfunction "1_1") (pintype "passive"))
    )
    (net (code "72") (name "Net-(ADC5-Pad1)") (class "Default")
      (node (ref "ADC5") (pin "1") (pinfunction "1_1") (pintype "passive"))
      (node (ref "R513") (pin "1") (pinfunction "1_1") (pintype "passive"))
    )
    (net (code "73") (name "Net-(ADC6-Pad1)") (class "Default")
      (node (ref "ADC6") (pin "1") (pinfunction "1_1") (pintype "passive"))
      (node (ref "R515") (pin "1") (pinfunction "1_1") (pintype "passive"))
    )
    (net (code "74") (name "Net-(ADC7-Pad1)") (class "Default")
      (node (ref "ADC7") (pin "1") (pinfunction "1_1") (pintype "passive"))
      (node (ref "R517") (pin "1") (pinfunction "1_1") (pintype "passive"))
    )
    (net (code "75") (name "Net-(D21-K)") (class "Default")
      (node (ref "D21") (pin "2") (pinfunction "K_2") (pintype "passive"))
      (node (ref "L10") (pin "1") (pinfunction "1_1") (pintype "passive"))
      (node (ref "U6") (pin "2") (pinfunction "Out_2") (pintype "output"))
    )
    (net (code "76") (name "Net-(LED20-K)") (class "Default")
      (node (ref "LED20") (pin "2") (pinfunction "K_2") (pintype "passive"))
      (node (ref "R10") (pin "2") (pinfunction "2_2") (pintype "passive"))
    )
    (net (code "77") (name "Net-(LED301-Pad1)") (class "Default")
      (node (ref "LED301") (pin "1") (pinfunction "1_1") (pintype "passive"))
      (node (ref "R301") (pin "1") (pinfunction "1_1") (pintype "passive"))
    )
    (net (code "78") (name "Net-(LED302-Pad1)") (class "Default")
      (node (ref "LED302") (pin "1") (pinfunction "1_1") (pintype "passive"))
      (node (ref "R302") (pin "1") (pinfunction "1_1") (pintype "passive"))
    )
    (net (code "79") (name "Net-(LED600-Pad1)") (class "Default")
      (node (ref "LED600") (pin "1") (pinfunction "1_1") (pintype "passive"))
      (node (ref "R11") (pin "1") (pinfunction "1_1") (pintype "passive"))
    )
    (net (code "80") (name "Net-(LED601-Pad1)") (class "Default")
      (node (ref "LED601") (pin "1") (pinfunction "1_1") (pintype "passive"))
      (node (ref "R12") (pin "1") (pinfunction "1_1") (pintype "passive"))
    )
    (net (code "81") (name "Net-(LED602-Pad1)") (class "Default")
      (node (ref "LED602") (pin "1") (pinfunction "1_1") (pintype "passive"))
      (node (ref "R13") (pin "1") (pinfunction "1_1") (pintype "passive"))
    )
    (net (code "82") (name "Net-(LED603-Pad1)") (class "Default")
      (node (ref "LED603") (pin "1") (pinfunction "1_1") (pintype "passive"))
      (node (ref "R14") (pin "1") (pinfunction "1_1") (pintype "passive"))
    )
    (net (code "83") (name "Net-(LED720-Pad1)") (class "Default")
      (node (ref "LED720") (pin "1") (pinfunction "1_1") (pintype "passive"))
      (node (ref "R720") (pin "2") (pinfunction "2_2") (pintype "passive"))
    )
    (net (code "84") (name "Net-(LED721-Pad1)") (class "Default")
      (node (ref "LED721") (pin "1") (pinfunction "1_1") (pintype "passive"))
      (node (ref "R721") (pin "2") (pinfunction "2_2") (pintype "passive"))
    )
    (net (code "85") (name "Net-(LED722-Pad1)") (class "Default")
      (node (ref "LED722") (pin "1") (pinfunction "1_1") (pintype "passive"))
      (node (ref "R722") (pin "2") (pinfunction "2_2") (pintype "passive"))
    )
    (net (code "86") (name "Net-(LED723-Pad1)") (class "Default")
      (node (ref "LED723") (pin "1") (pinfunction "1_1") (pintype "passive"))
      (node (ref "R723") (pin "2") (pinfunction "2_2") (pintype "passive"))
    )
    (net (code "87") (name "Net-(LED724-Pad1)") (class "Default")
      (node (ref "LED724") (pin "1") (pinfunction "1_1") (pintype "passive"))
      (node (ref "R724") (pin "2") (pinfunction "2_2") (pintype "passive"))
    )
    (net (code "88") (name "Net-(LED725-Pad1)") (class "Default")
      (node (ref "LED725") (pin "1") (pinfunction "1_1") (pintype "passive"))
      (node (ref "R725") (pin "2") (pinfunction "2_2") (pintype "passive"))
    )
    (net (code "89") (name "Net-(LED726-Pad1)") (class "Default")
      (node (ref "LED726") (pin "1") (pinfunction "1_1") (pintype "passive"))
      (node (ref "R726") (pin "2") (pinfunction "2_2") (pintype "passive"))
    )
    (net (code "90") (name "Net-(LED727-Pad1)") (class "Default")
      (node (ref "LED727") (pin "1") (pinfunction "1_1") (pintype "passive"))
      (node (ref "R727") (pin "2") (pinfunction "2_2") (pintype "passive"))
    )
    (net (code "91") (name "Net-(Q1-B)") (class "Default")
      (node (ref "Q1") (pin "1") (pinfunction "B_1") (pintype "passive"))
      (node (ref "Q2") (pin "3") (pinfunction "C_3") (pintype "passive"))
      (node (ref "R601") (pin "1") (pinfunction "1_1") (pintype "passive"))
    )
    (net (code "92") (name "Net-(Q1-C)") (class "Default")
      (node (ref "LED600") (pin "2") (pinfunction "2_2") (pintype "passive"))
      (node (ref "Q1") (pin "3") (pinfunction "C_3") (pintype "passive"))
      (node (ref "RELAY1") (pin "1") (pinfunction "1_1") (pintype "passive"))
    )
    (net (code "93") (name "Net-(Q3-B)") (class "Default")
      (node (ref "Q3") (pin "1") (pinfunction "B_1") (pintype "passive"))
      (node (ref "Q4") (pin "3") (pinfunction "C_3") (pintype "passive"))
      (node (ref "R602") (pin "2") (pinfunction "2_2") (pintype "passive"))
    )
    (net (code "94") (name "Net-(Q3-C)") (class "Default")
      (node (ref "LED601") (pin "2") (pinfunction "2_2") (pintype "passive"))
      (node (ref "Q3") (pin "3") (pinfunction "C_3") (pintype "passive"))
      (node (ref "RELAY2") (pin "1") (pinfunction "1_1") (pintype "passive"))
    )
    (net (code "95") (name "Net-(Q5-B)") (class "Default")
      (node (ref "Q5") (pin "1") (pinfunction "B_1") (pintype "passive"))
      (node (ref "Q6") (pin "3") (pinfunction "C_3") (pintype "passive"))
      (node (ref "R603") (pin "2") (pinfunction "2_2") (pintype "passive"))
    )
    (net (code "96") (name "Net-(Q5-C)") (class "Default")
      (node (ref "LED602") (pin "2") (pinfunction "2_2") (pintype "passive"))
      (node (ref "Q5") (pin "3") (pinfunction "C_3") (pintype "passive"))
      (node (ref "RELAY3") (pin "1") (pinfunction "1_1") (pintype "passive"))
    )
    (net (code "97") (name "Net-(Q7-B)") (class "Default")
      (node (ref "Q7") (pin "1") (pinfunction "B_1") (pintype "passive"))
      (node (ref "Q8") (pin "3") (pinfunction "C_3") (pintype "passive"))
      (node (ref "R604") (pin "2") (pinfunction "2_2") (pintype "passive"))
    )
    (net (code "98") (name "Net-(Q7-C)") (class "Default")
      (node (ref "LED603") (pin "2") (pinfunction "2_2") (pintype "passive"))
      (node (ref "Q7") (pin "3") (pinfunction "C_3") (pintype "passive"))
      (node (ref "RELAY4") (pin "1") (pinfunction "1_1") (pintype "passive"))
    )
    (net (code "99") (name "Net-(U11-A)") (class "Default")
      (node (ref "R701") (pin "2") (pinfunction "2_2") (pintype "passive"))
      (node (ref "U11") (pin "1") (pinfunction "A_1") (pintype "passive"))
    )
    (net (code "100") (name "Net-(U12-A)") (class "Default")
      (node (ref "R702") (pin "2") (pinfunction "2_2") (pintype "passive"))
      (node (ref "U12") (pin "1") (pinfunction "A_1") (pintype "passive"))
    )
    (net (code "101") (name "Net-(U13-A)") (class "Default")
      (node (ref "R703") (pin "2") (pinfunction "2_2") (pintype "passive"))
      (node (ref "U13") (pin "1") (pinfunction "A_1") (pintype "passive"))
    )
    (net (code "102") (name "Net-(U14-A)") (class "Default")
      (node (ref "R704") (pin "2") (pinfunction "2_2") (pintype "passive"))
      (node (ref "U14") (pin "1") (pinfunction "A_1") (pintype "passive"))
    )
    (net (code "103") (name "Net-(U15-A)") (class "Default")
      (node (ref "R705") (pin "2") (pinfunction "2_2") (pintype "passive"))
      (node (ref "U15") (pin "1") (pinfunction "A_1") (pintype "passive"))
    )
    (net (code "104") (name "Net-(U16-A)") (class "Default")
      (node (ref "R706") (pin "2") (pinfunction "2_2") (pintype "passive"))
      (node (ref "U16") (pin "1") (pinfunction "A_1") (pintype "passive"))
    )
    (net (code "105") (name "Net-(U17-A)") (class "Default")
      (node (ref "R707") (pin "2") (pinfunction "2_2") (pintype "passive"))
      (node (ref "U17") (pin "1") (pinfunction "A_1") (pintype "passive"))
    )
    (net (code "106") (name "Net-(U18-A)") (class "Default")
      (node (ref "R708") (pin "2") (pinfunction "2_2") (pintype "passive"))
      (node (ref "U18") (pin "1") (pinfunction "A_1") (pintype "passive"))
    )
    (net (code "107") (name "Net-(U100-V3)") (class "Default")
      (node (ref "C304") (pin "2") (pinfunction "2_2") (pintype "passive"))
      (node (ref "U100") (pin "4") (pinfunction "V3_4") (pintype "passive"))
    )
    (net (code "108") (name "Net-(U100-XI)") (class "Default")
      (node (ref "C301") (pin "1") (pinfunction "1_1") (pintype "passive"))
      (node (ref "U100") (pin "7") (pinfunction "XI_7") (pintype "passive"))
      (node (ref "Y20") (pin "1") (pinfunction "1_1") (pintype "passive"))
    )
    (net (code "109") (name "Net-(U100-XO)") (class "Default")
      (node (ref "C302") (pin "1") (pinfunction "1_1") (pintype "passive"))
      (node (ref "U100") (pin "8") (pinfunction "XO_8") (pintype "passive"))
      (node (ref "Y20") (pin "2") (pinfunction "2_2") (pintype "passive"))
    )
    (net (code "110") (name "POWER_OUT") (class "Default")
      (node (ref "C10") (pin "1") (pinfunction "1_1") (pintype "passive"))
      (node (ref "POWER") (pin "1") (pinfunction "1_1") (pintype "passive"))
      (node (ref "R701") (pin "1") (pinfunction "1_1") (pintype "passive"))
      (node (ref "R702") (pin "1") (pinfunction "1_1") (pintype "passive"))
      (node (ref "R703") (pin "1") (pinfunction "1_1") (pintype "passive"))
      (node (ref "R704") (pin "1") (pinfunction "1_1") (pintype "passive"))
      (node (ref "R705") (pin "1") (pinfunction "1_1") (pintype "passive"))
      (node (ref "R706") (pin "1") (pinfunction "1_1") (pintype "passive"))
      (node (ref "R707") (pin "1") (pinfunction "1_1") (pintype "passive"))
      (node (ref "R708") (pin "1") (pinfunction "1_1") (pintype "passive"))
      (node (ref "U6") (pin "1") (pinfunction "+VIN_1") (pintype "input"))
    )
    (net (code "111") (name "PVCC") (class "Default")
      (node (ref "C11") (pin "1") (pinfunction "1_1") (pintype "passive"))
      (node (ref "L10") (pin "2") (pinfunction "2_2") (pintype "passive"))
      (node (ref "S1") (pin "3") (pinfunction "3_3") (pintype "passive"))
      (node (ref "U6") (pin "4") (pinfunction "Feedback_4") (pintype "input"))
    )
    (net (code "112") (name "USB5V") (class "Default")
      (node (ref "S1") (pin "1") (pinfunction "1_1") (pintype "passive"))
      (node (ref "USART") (pin "1") (pinfunction "1_1") (pintype "passive"))
    )
    (net (code "113") (name "VCC") (class "Default")
      (node (ref "C303") (pin "1") (pinfunction "1_1") (pintype "passive"))
      (node (ref "LED20") (pin "1") (pinfunction "A_1") (pintype "passive"))
      (node (ref "P2") (pin "1") (pinfunction "1_1") (pintype "passive"))
      (node (ref "P3") (pin "1") (pinfunction "1_1") (pintype "passive"))
      (node (ref "P3") (pin "2") (pinfunction "2_2") (pintype "passive"))
      (node (ref "R11") (pin "2") (pinfunction "2_2") (pintype "passive"))
      (node (ref "R12") (pin "2") (pinfunction "2_2") (pintype "passive"))
      (node (ref "R13") (pin "2") (pinfunction "2_2") (pintype "passive"))
      (node (ref "R14") (pin "2") (pinfunction "2_2") (pintype "passive"))
      (node (ref "R26") (pin "2") (pinfunction "2_2") (pintype "passive"))
      (node (ref "R27") (pin "2") (pinfunction "2_2") (pintype "passive"))
      (node (ref "R301") (pin "2") (pinfunction "2_2") (pintype "passive"))
      (node (ref "R302") (pin "2") (pinfunction "2_2") (pintype "passive"))
      (node (ref "R45") (pin "2") (pinfunction "2_2") (pintype "passive"))
      (node (ref "R46") (pin "2") (pinfunction "2_2") (pintype "passive"))
      (node (ref "R601") (pin "2") (pinfunction "2_2") (pintype "passive"))
      (node (ref "R602") (pin "1") (pinfunction "1_1") (pintype "passive"))
      (node (ref "R603") (pin "1") (pinfunction "1_1") (pintype "passive"))
      (node (ref "R604") (pin "1") (pinfunction "1_1") (pintype "passive"))
      (node (ref "R720") (pin "1") (pinfunction "1_1") (pintype "passive"))
      (node (ref "R721") (pin "1") (pinfunction "1_1") (pintype "passive"))
      (node (ref "R722") (pin "1") (pinfunction "1_1") (pintype "passive"))
      (node (ref "R723") (pin "1") (pinfunction "1_1") (pintype "passive"))
      (node (ref "R724") (pin "1") (pinfunction "1_1") (pintype "passive"))
      (node (ref "R725") (pin "1") (pinfunction "1_1") (pintype "passive"))
      (node (ref "R726") (pin "1") (pinfunction "1_1") (pintype "passive"))
      (node (ref "R727") (pin "1") (pinfunction "1_1") (pintype "passive"))
      (node (ref "RELAY1") (pin "2") (pinfunction "2_2") (pintype "passive"))
      (node (ref "RELAY2") (pin "2") (pinfunction "2_2") (pintype "passive"))
      (node (ref "RELAY3") (pin "2") (pinfunction "2_2") (pintype "passive"))
      (node (ref "RELAY4") (pin "2") (pinfunction "2_2") (pintype "passive"))
      (node (ref "S1") (pin "2") (pinfunction "2_2") (pintype "passive"))
      (node (ref "SW") (pin "2") (pinfunction "2_2") (pintype "passive"))
      (node (ref "SW") (pin "5") (pinfunction "5_5") (pintype "passive"))
      (node (ref "U100") (pin "16") (pinfunction "VCC_16") (pintype "power_in"))
    )
    (net (code "114") (name "unconnected-(SW-Pad1)") (class "Default")
      (node (ref "SW") (pin "1") (pinfunction "1_1") (pintype "passive"))
    )
    (net (code "115") (name "unconnected-(SW-Pad4)") (class "Default")
      (node (ref "SW") (pin "4") (pinfunction "4_4") (pintype "passive"))
    )
    (net (code "116") (name "unconnected-(U100-CTS#-Pad9)") (class "Default")
      (node (ref "U100") (pin "9") (pinfunction "CTS#_9") (pintype "passive"))
    )
    (net (code "117") (name "unconnected-(U100-DCD#-Pad12)") (class "Default")
      (node (ref "U100") (pin "12") (pinfunction "DCD#_12") (pintype "passive"))
    )
    (net (code "118") (name "unconnected-(U100-DSR#-Pad10)") (class "Default")
      (node (ref "U100") (pin "10") (pinfunction "DSR#_10") (pintype "passive"))
    )
    (net (code "119") (name "unconnected-(U100-DTR#-Pad13)") (class "Default")
      (node (ref "U100") (pin "13") (pinfunction "DTR#_13") (pintype "passive"))
    )
    (net (code "120") (name "unconnected-(U100-RI#-Pad11)") (class "Default")
      (node (ref "U100") (pin "11") (pinfunction "RI#_11") (pintype "passive"))
    )
    (net (code "121") (name "unconnected-(U100-RS232-Pad15)") (class "Default")
      (node (ref "U100") (pin "15") (pinfunction "RS232_15") (pintype "passive"))
    )
    (net (code "122") (name "unconnected-(U100-RST#-Pad14)") (class "Default")
      (node (ref "U100") (pin "14") (pinfunction "RST#_14") (pintype "passive"))
    )
  )
)
